# 09-NORStatusLed.net
KiCad netlist of a schematic drawn in Altium Designer
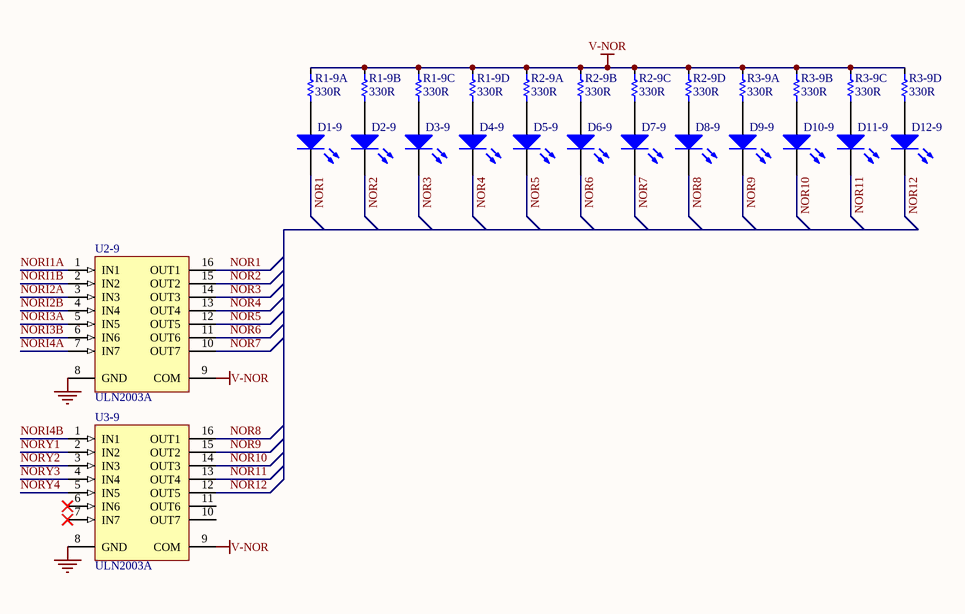
[diagram p0: 09-NORStatusLed.SchDoc]

(export (version "E")
  (design (tool "Eeschema 10.0.6"))
  (components
    (comp (ref "D1-9")
      (value "LED")
      (footprint "LED-0805")
      (description "Typical RED, GREEN, YELLOW, AMBER GaAs LED")
      (fields (field (name "PUBLISHER") "Altium Limited"))
      (libsource (lib "Miscellaneous Devices") (part "LED2"))
    )
    (comp (ref "D2-9")
      (value "LED")
      (footprint "LED-0805")
      (description "Typical RED, GREEN, YELLOW, AMBER GaAs LED")
      (fields (field (name "PUBLISHER") "Altium Limited"))
      (libsource (lib "Miscellaneous Devices") (part "LED2"))
    )
    (comp (ref "D3-9")
      (value "LED")
      (footprint "LED-0805")
      (description "Typical RED, GREEN, YELLOW, AMBER GaAs LED")
      (fields (field (name "PUBLISHER") "Altium Limited"))
      (libsource (lib "Miscellaneous Devices") (part "LED2"))
    )
    (comp (ref "D4-9")
      (value "LED")
      (footprint "LED-0805")
      (description "Typical RED, GREEN, YELLOW, AMBER GaAs LED")
      (fields (field (name "PUBLISHER") "Altium Limited"))
      (libsource (lib "Miscellaneous Devices") (part "LED2"))
    )
    (comp (ref "D5-9")
      (value "LED")
      (footprint "LED-0805")
      (description "Typical RED, GREEN, YELLOW, AMBER GaAs LED")
      (fields (field (name "PUBLISHER") "Altium Limited"))
      (libsource (lib "Miscellaneous Devices") (part "LED2"))
    )
    (comp (ref "D6-9")
      (value "LED")
      (footprint "LED-0805")
      (description "Typical RED, GREEN, YELLOW, AMBER GaAs LED")
      (fields (field (name "PUBLISHER") "Altium Limited"))
      (libsource (lib "Miscellaneous Devices") (part "LED2"))
    )
    (comp (ref "D7-9")
      (value "LED")
      (footprint "LED-0805")
      (description "Typical RED, GREEN, YELLOW, AMBER GaAs LED")
      (fields (field (name "PUBLISHER") "Altium Limited"))
      (libsource (lib "Miscellaneous Devices") (part "LED2"))
    )
    (comp (ref "D8-9")
      (value "LED")
      (footprint "LED-0805")
      (description "Typical RED, GREEN, YELLOW, AMBER GaAs LED")
      (fields (field (name "PUBLISHER") "Altium Limited"))
      (libsource (lib "Miscellaneous Devices") (part "LED2"))
    )
    (comp (ref "D9-9")
      (value "LED")
      (footprint "LED-0805")
      (description "Typical RED, GREEN, YELLOW, AMBER GaAs LED")
      (fields (field (name "PUBLISHER") "Altium Limited"))
      (libsource (lib "Miscellaneous Devices") (part "LED2"))
    )
    (comp (ref "D10-9")
      (value "LED")
      (footprint "LED-0805")
      (description "Typical RED, GREEN, YELLOW, AMBER GaAs LED")
      (fields (field (name "PUBLISHER") "Altium Limited"))
      (libsource (lib "Miscellaneous Devices") (part "LED2"))
    )
    (comp (ref "D11-9")
      (value "LED")
      (footprint "LED-0805")
      (description "Typical RED, GREEN, YELLOW, AMBER GaAs LED")
      (fields (field (name "PUBLISHER") "Altium Limited"))
      (libsource (lib "Miscellaneous Devices") (part "LED2"))
    )
    (comp (ref "D12-9")
      (value "LED")
      (footprint "LED-0805")
      (description "Typical RED, GREEN, YELLOW, AMBER GaAs LED")
      (fields (field (name "PUBLISHER") "Altium Limited"))
      (libsource (lib "Miscellaneous Devices") (part "LED2"))
    )
    (comp (ref "R1-9")
      (value "330R")
      (footprint "R-Array-0603-4")
      (description "RES ARRAY 4 RES 330 OHM 1206")
      (fields
        (field (name "DIGI-KEY PART NUMBER") "Y9331TR-ND")
        (field (name "MANUFACTURER") "Panasonic Electronic Components")
      )
      (libsource (lib "Dlib") (part "Res Array 4"))
    )
    (comp (ref "R2-9")
      (value "330R")
      (footprint "R-Array-0603-4")
      (description "RES ARRAY 4 RES 330 OHM 1206")
      (fields
        (field (name "DIGI-KEY PART NUMBER") "Y9331TR-ND")
        (field (name "MANUFACTURER") "Panasonic Electronic Components")
      )
      (libsource (lib "Dlib") (part "Res Array 4"))
    )
    (comp (ref "R3-9")
      (value "330R")
      (footprint "R-Array-0603-4")
      (description "RES ARRAY 4 RES 330 OHM 1206")
      (fields
        (field (name "DIGI-KEY PART NUMBER") "Y9331TR-ND")
        (field (name "MANUFACTURER") "Panasonic Electronic Components")
      )
      (libsource (lib "Dlib") (part "Res Array 4"))
    )
    (comp (ref "U2-9")
      (value "ULN2003A")
      (footprint "SOIC-16")
      (description "High-Voltage, High-Current Darlington Array")
      (fields (field (name "PUBLISHER") "Altium Limited"))
      (libsource (lib "Allegro Interface Darlington Driver") (part "ULN2003A"))
    )
    (comp (ref "U3-9")
      (value "ULN2003A")
      (footprint "SOIC-16")
      (description "High-Voltage, High-Current Darlington Array")
      (fields (field (name "PUBLISHER") "Altium Limited"))
      (libsource (lib "Allegro Interface Darlington Driver") (part "ULN2003A"))
    )
  )
  (nets
    (net (code "1") (name "/NOR1") (class "Default")
      (node (ref "D1-9") (pin "2") (pinfunction "K_2") (pintype "passive"))
      (node (ref "U2-9") (pin "16") (pinfunction "OUT1_16") (pintype "open_collector"))
    )
    (net (code "2") (name "/NOR2") (class "Default")
      (node (ref "D2-9") (pin "2") (pinfunction "K_2") (pintype "passive"))
      (node (ref "U2-9") (pin "15") (pinfunction "OUT2_15") (pintype "open_collector"))
    )
    (net (code "3") (name "/NOR3") (class "Default")
      (node (ref "D3-9") (pin "2") (pinfunction "K_2") (pintype "passive"))
      (node (ref "U2-9") (pin "14") (pinfunction "OUT3_14") (pintype "open_collector"))
    )
    (net (code "4") (name "/NOR4") (class "Default")
      (node (ref "D4-9") (pin "2") (pinfunction "K_2") (pintype "passive"))
      (node (ref "U2-9") (pin "13") (pinfunction "OUT4_13") (pintype "open_collector"))
    )
    (net (code "5") (name "/NOR5") (class "Default")
      (node (ref "D5-9") (pin "2") (pinfunction "K_2") (pintype "passive"))
      (node (ref "U2-9") (pin "12") (pinfunction "OUT5_12") (pintype "open_collector"))
    )
    (net (code "6") (name "/NOR6") (class "Default")
      (node (ref "D6-9") (pin "2") (pinfunction "K_2") (pintype "passive"))
      (node (ref "U2-9") (pin "11") (pinfunction "OUT6_11") (pintype "open_collector"))
    )
    (net (code "7") (name "/NOR7") (class "Default")
      (node (ref "D7-9") (pin "2") (pinfunction "K_2") (pintype "passive"))
      (node (ref "U2-9") (pin "10") (pinfunction "OUT7_10") (pintype "open_collector"))
    )
    (net (code "8") (name "/NOR8") (class "Default")
      (node (ref "D8-9") (pin "2") (pinfunction "K_2") (pintype "passive"))
      (node (ref "U3-9") (pin "16") (pinfunction "OUT1_16") (pintype "open_collector"))
    )
    (net (code "9") (name "/NOR9") (class "Default")
      (node (ref "D9-9") (pin "2") (pinfunction "K_2") (pintype "passive"))
      (node (ref "U3-9") (pin "15") (pinfunction "OUT2_15") (pintype "open_collector"))
    )
    (net (code "10") (name "/NOR10") (class "Default")
      (node (ref "D10-9") (pin "2") (pinfunction "K_2") (pintype "passive"))
      (node (ref "U3-9") (pin "14") (pinfunction "OUT3_14") (pintype "open_collector"))
    )
    (net (code "11") (name "/NOR11") (class "Default")
      (node (ref "D11-9") (pin "2") (pinfunction "K_2") (pintype "passive"))
      (node (ref "U3-9") (pin "13") (pinfunction "OUT4_13") (pintype "open_collector"))
    )
    (net (code "12") (name "/NOR12") (class "Default")
      (node (ref "D12-9") (pin "2") (pinfunction "K_2") (pintype "passive"))
      (node (ref "U3-9") (pin "12") (pinfunction "OUT5_12") (pintype "open_collector"))
    )
    (net (code "13") (name "/NORI1A") (class "Default")
      (node (ref "U2-9") (pin "1") (pinfunction "IN1_1") (pintype "input"))
    )
    (net (code "14") (name "/NORI1B") (class "Default")
      (node (ref "U2-9") (pin "2") (pinfunction "IN2_2") (pintype "input"))
    )
    (net (code "15") (name "/NORI2A") (class "Default")
      (node (ref "U2-9") (pin "3") (pinfunction "IN3_3") (pintype "input"))
    )
    (net (code "16") (name "/NORI2B") (class "Default")
      (node (ref "U2-9") (pin "4") (pinfunction "IN4_4") (pintype "input"))
    )
    (net (code "17") (name "/NORI3A") (class "Default")
      (node (ref "U2-9") (pin "5") (pinfunction "IN5_5") (pintype "input"))
    )
    (net (code "18") (name "/NORI3B") (class "Default")
      (node (ref "U2-9") (pin "6") (pinfunction "IN6_6") (pintype "input"))
    )
    (net (code "19") (name "/NORI4A") (class "Default")
      (node (ref "U2-9") (pin "7") (pinfunction "IN7_7") (pintype "input"))
    )
    (net (code "20") (name "/NORI4B") (class "Default")
      (node (ref "U3-9") (pin "1") (pinfunction "IN1_1") (pintype "input"))
    )
    (net (code "21") (name "/NORY1") (class "Default")
      (node (ref "U3-9") (pin "2") (pinfunction "IN2_2") (pintype "input"))
    )
    (net (code "22") (name "/NORY2") (class "Default")
      (node (ref "U3-9") (pin "3") (pinfunction "IN3_3") (pintype "input"))
    )
    (net (code "23") (name "/NORY3") (class "Default")
      (node (ref "U3-9") (pin "4") (pinfunction "IN4_4") (pintype "input"))
    )
    (net (code "24") (name "/NORY4") (class "Default")
      (node (ref "U3-9") (pin "5") (pinfunction "IN5_5") (pintype "input"))
    )
    (net (code "25") (name "GND") (class "Default")
      (node (ref "U2-9") (pin "8") (pinfunction "GND_8") (pintype "power_in"))
      (node (ref "U3-9") (pin "8") (pinfunction "GND_8") (pintype "power_in"))
    )
    (net (code "26") (name "Net-(D1-9-A)") (class "Default")
      (node (ref "D1-9") (pin "1") (pinfunction "A_1") (pintype "passive"))
      (node (ref "R1-9") (pin "1") (pinfunction "1_1") (pintype "passive"))
    )
    (net (code "27") (name "Net-(D2-9-A)") (class "Default")
      (node (ref "D2-9") (pin "1") (pinfunction "A_1") (pintype "passive"))
      (node (ref "R1-9") (pin "3") (pinfunction "1_3") (pintype "passive"))
    )
    (net (code "28") (name "Net-(D3-9-A)") (class "Default")
      (node (ref "D3-9") (pin "1") (pinfunction "A_1") (pintype "passive"))
      (node (ref "R1-9") (pin "5") (pinfunction "1_5") (pintype "passive"))
    )
    (net (code "29") (name "Net-(D4-9-A)") (class "Default")
      (node (ref "D4-9") (pin "1") (pinfunction "A_1") (pintype "passive"))
      (node (ref "R1-9") (pin "7") (pinfunction "1_7") (pintype "passive"))
    )
    (net (code "30") (name "Net-(D5-9-A)") (class "Default")
      (node (ref "D5-9") (pin "1") (pinfunction "A_1") (pintype "passive"))
      (node (ref "R2-9") (pin "1") (pinfunction "1_1") (pintype "passive"))
    )
    (net (code "31") (name "Net-(D6-9-A)") (class "Default")
      (node (ref "D6-9") (pin "1") (pinfunction "A_1") (pintype "passive"))
      (node (ref "R2-9") (pin "3") (pinfunction "1_3") (pintype "passive"))
    )
    (net (code "32") (name "Net-(D7-9-A)") (class "Default")
      (node (ref "D7-9") (pin "1") (pinfunction "A_1") (pintype "passive"))
      (node (ref "R2-9") (pin "5") (pinfunction "1_5") (pintype "passive"))
    )
    (net (code "33") (name "Net-(D8-9-A)") (class "Default")
      (node (ref "D8-9") (pin "1") (pinfunction "A_1") (pintype "passive"))
      (node (ref "R2-9") (pin "7") (pinfunction "1_7") (pintype "passive"))
    )
    (net (code "34") (name "Net-(D9-9-A)") (class "Default")
      (node (ref "D9-9") (pin "1") (pinfunction "A_1") (pintype "passive"))
      (node (ref "R3-9") (pin "1") (pinfunction "1_1") (pintype "passive"))
    )
    (net (code "35") (name "Net-(D10-9-A)") (class "Default")
      (node (ref "D10-9") (pin "1") (pinfunction "A_1") (pintype "passive"))
      (node (ref "R3-9") (pin "3") (pinfunction "1_3") (pintype "passive"))
    )
    (net (code "36") (name "Net-(D11-9-A)") (class "Default")
      (node (ref "D11-9") (pin "1") (pinfunction "A_1") (pintype "passive"))
      (node (ref "R3-9") (pin "5") (pinfunction "1_5") (pintype "passive"))
    )
    (net (code "37") (name "Net-(D12-9-A)") (class "Default")
      (node (ref "D12-9") (pin "1") (pinfunction "A_1") (pintype "passive"))
      (node (ref "R3-9") (pin "7") (pinfunction "1_7") (pintype "passive"))
    )
    (net (code "38") (name "V-NOR") (class "Default")
      (node (ref "R1-9") (pin "2") (pinfunction "2_2") (pintype "passive"))
      (node (ref "R1-9") (pin "4") (pinfunction "2_4") (pintype "passive"))
      (node (ref "R1-9") (pin "6") (pinfunction "2_6") (pintype "passive"))
      (node (ref "R1-9") (pin "8") (pinfunction "2_8") (pintype "passive"))
      (node (ref "R2-9") (pin "2") (pinfunction "2_2") (pintype "passive"))
      (node (ref "R2-9") (pin "4") (pinfunction "2_4") (pintype "passive"))
      (node (ref "R2-9") (pin "6") (pinfunction "2_6") (pintype "passive"))
      (node (ref "R2-9") (pin "8") (pinfunction "2_8") (pintype "passive"))
      (node (ref "R3-9") (pin "2") (pinfunction "2_2") (pintype "passive"))
      (node (ref "R3-9") (pin "4") (pinfunction "2_4") (pintype "passive"))
      (node (ref "R3-9") (pin "6") (pinfunction "2_6") (pintype "passive"))
      (node (ref "R3-9") (pin "8") (pinfunction "2_8") (pintype "passive"))
      (node (ref "U2-9") (pin "9") (pinfunction "COM_9") (pintype "passive"))
      (node (ref "U3-9") (pin "9") (pinfunction "COM_9") (pintype "passive"))
    )
    (net (code "39") (name "unconnected-(U3-9-IN6-Pad6)") (class "Default")
      (node (ref "U3-9") (pin "6") (pinfunction "IN6_6") (pintype "input+no_connect"))
    )
    (net (code "40") (name "unconnected-(U3-9-IN7-Pad7)") (class "Default")
      (node (ref "U3-9") (pin "7") (pinfunction "IN7_7") (pintype "input+no_connect"))
    )
    (net (code "41") (name "unconnected-(U3-9-OUT6-Pad11)") (class "Default")
      (node (ref "U3-9") (pin "11") (pinfunction "OUT6_11") (pintype "open_collector"))
    )
    (net (code "42") (name "unconnected-(U3-9-OUT7-Pad10)") (class "Default")
      (node (ref "U3-9") (pin "10") (pinfunction "OUT7_10") (pintype "open_collector"))
    )
  )
)
